# Light_bar_-_half.net
KiCad netlist of a schematic drawn in EAGLE
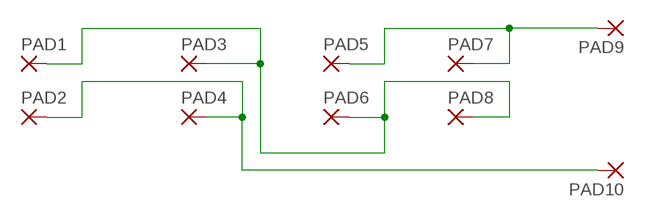
[diagram p0: schematic, sheet 1]

(export (version "E")
  (design (tool "Eeschema 10.0.6"))
  (components
    (comp (ref "PAD1")
      (value "SMD2")
      (footprint "eagle-import:SMD1,27-2,54")
      (libsource (lib "eagle-import") (part "SMD2"))
    )
    (comp (ref "PAD2")
      (value "SMD2")
      (footprint "eagle-import:SMD1,27-2,54")
      (libsource (lib "eagle-import") (part "SMD2"))
    )
    (comp (ref "PAD3")
      (value "SMD2")
      (footprint "eagle-import:SMD1,27-2,54")
      (libsource (lib "eagle-import") (part "SMD2"))
    )
    (comp (ref "PAD4")
      (value "SMD2")
      (footprint "eagle-import:SMD1,27-2,54")
      (libsource (lib "eagle-import") (part "SMD2"))
    )
    (comp (ref "PAD5")
      (value "SMD2")
      (footprint "eagle-import:SMD1,27-2,54")
      (libsource (lib "eagle-import") (part "SMD2"))
    )
    (comp (ref "PAD6")
      (value "SMD2")
      (footprint "eagle-import:SMD1,27-2,54")
      (libsource (lib "eagle-import") (part "SMD2"))
    )
    (comp (ref "PAD7")
      (value "SMD2")
      (footprint "eagle-import:SMD1,27-2,54")
      (libsource (lib "eagle-import") (part "SMD2"))
    )
    (comp (ref "PAD8")
      (value "SMD2")
      (footprint "eagle-import:SMD1,27-2,54")
      (libsource (lib "eagle-import") (part "SMD2"))
    )
    (comp (ref "PAD9")
      (value "SMD5")
      (footprint "eagle-import:SMD2,54-5,08")
      (libsource (lib "eagle-import") (part "SMD5"))
    )
    (comp (ref "PAD10")
      (value "SMD5")
      (footprint "eagle-import:SMD2,54-5,08")
      (libsource (lib "eagle-import") (part "SMD5"))
    )
  )
  (nets
    (net (code "1") (name "Net-(PAD1-P)") (class "Default")
      (node (ref "PAD1") (pin "1") (pinfunction "P_1") (pintype "passive"))
      (node (ref "PAD3") (pin "1") (pinfunction "P_1") (pintype "passive"))
      (node (ref "PAD6") (pin "1") (pinfunction "P_1") (pintype "passive"))
      (node (ref "PAD8") (pin "1") (pinfunction "P_1") (pintype "passive"))
    )
    (net (code "2") (name "Net-(PAD5-P)") (class "Default")
      (node (ref "PAD5") (pin "1") (pinfunction "P_1") (pintype "passive"))
      (node (ref "PAD7") (pin "1") (pinfunction "P_1") (pintype "passive"))
      (node (ref "PAD9") (pin "1") (pinfunction "P_1") (pintype "passive"))
    )
    (net (code "3") (name "Net-(PAD10-P)") (class "Default")
      (node (ref "PAD10") (pin "1") (pinfunction "P_1") (pintype "passive"))
      (node (ref "PAD2") (pin "1") (pinfunction "P_1") (pintype "passive"))
      (node (ref "PAD4") (pin "1") (pinfunction "P_1") (pintype "passive"))
    )
  )
)
